# TIDA-00641_BlankSheet.net
KiCad netlist of a schematic drawn in Altium Designer
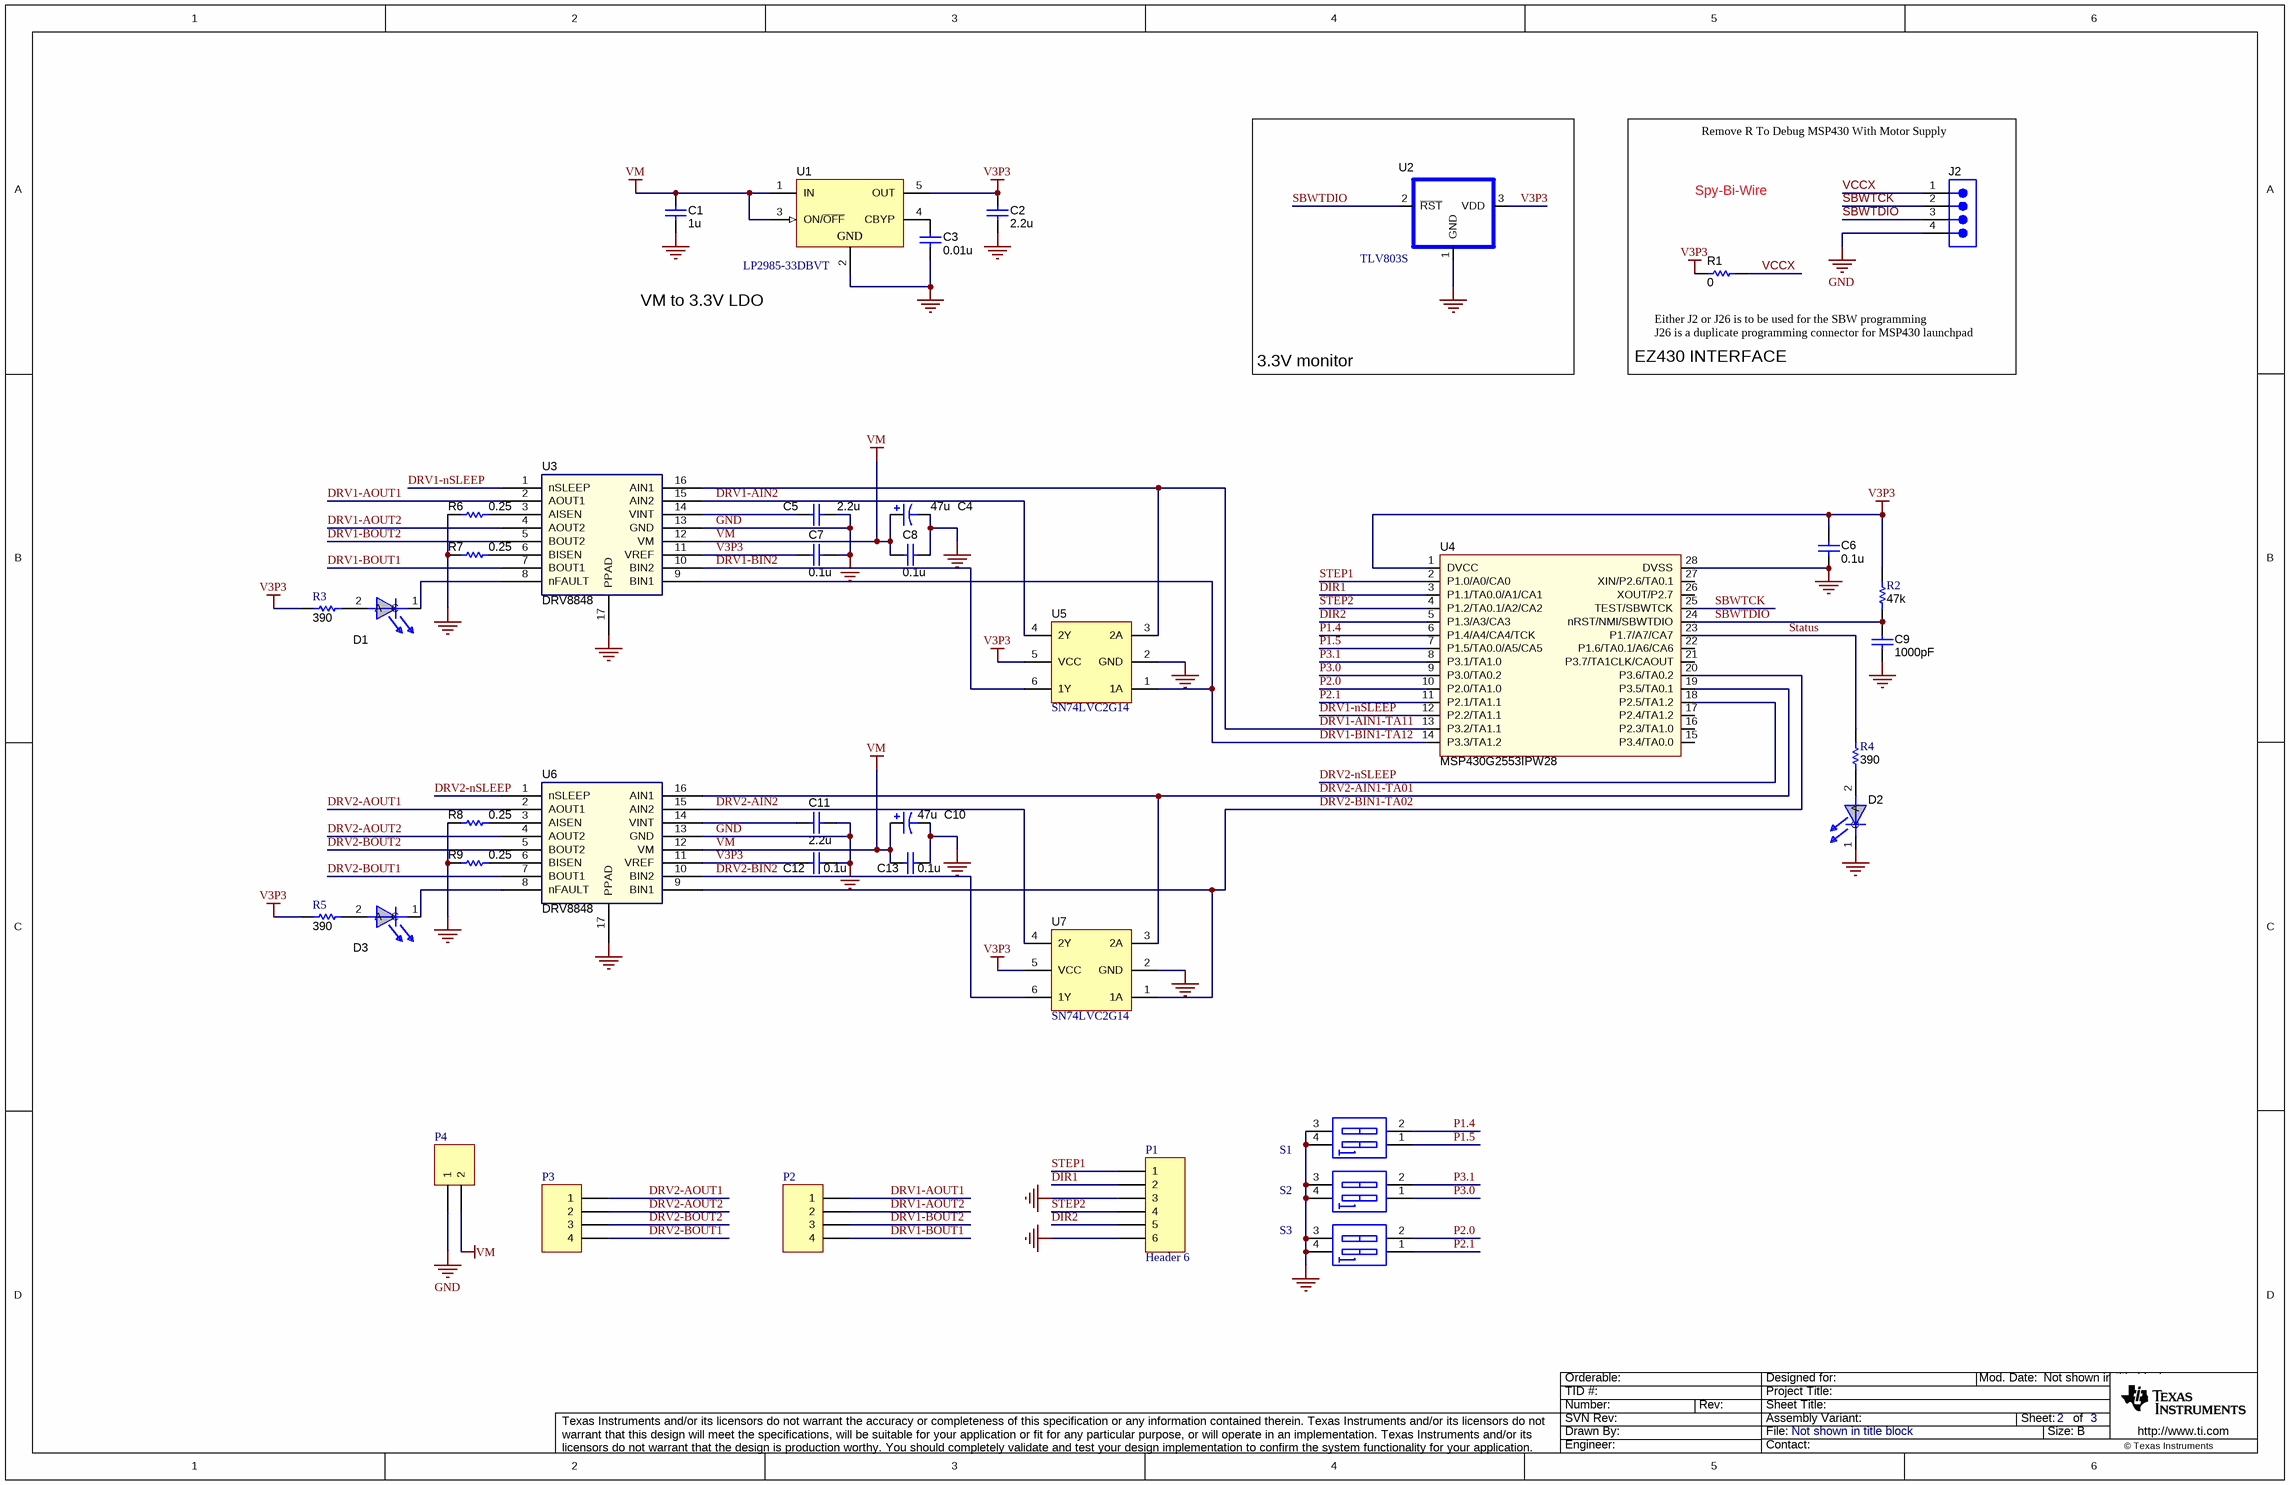
[diagram p0: TIDA-00641_BlankSheet.SchDoc]

(export (version "E")
  (design (tool "Eeschema 10.0.6"))
  (components
    (comp (ref "C1")
      (value "C0603C105K4PACTU")
      (footprint "0603L")
      (description "CAP, CERM, 1uF, 16V, +/-10%, X5R, 0603")
      (fields
        (field (name "MANUFACTURER") "Kemet")
        (field (name "VALUEDISPLAYED") "1u")
        (field (name "PUBLISHER") "Texas Instruments")
      )
      (libsource (lib "Capacitor_Ceramic") (part "C0603C105K4PACTU"))
    )
    (comp (ref "C2")
      (value "C0603C225K8PACTU")
      (footprint "0603L")
      (description "CAP, CERM, 2.2uF, 10V, +/-10%, X5R, 0603")
      (fields
        (field (name "VALUEDISPLAYED") "2.2u")
        (field (name "MANUFACTURER") "Kemet")
        (field (name "PUBLISHER") "Texas Instruments")
      )
      (libsource (lib "Capacitor_Ceramic") (part "C0603C225K8PACTU"))
    )
    (comp (ref "C3")
      (value "C0603C103J5RACTU")
      (footprint "0603L")
      (description "CAP, CERM, 0.01uF, 50V, +/-5%, X7R, 0603")
      (fields
        (field (name "MANUFACTURER") "Kemet")
        (field (name "VALUEDISPLAYED") "0.01u")
        (field (name "PUBLISHER") "Texas Instruments")
      )
      (libsource (lib "Capacitor_Ceramic") (part "C0603C103J5RACTU"))
    )
    (comp (ref "C4")
      (value "EEE-FK1E470P")
      (footprint "SM_RADIAL_D")
      (description "CAP, AL, 47uF, 25V, +/-20%, 0.36 ohm, SMD")
      (fields
        (field (name "VALUEDISPLAYED") "47u")
        (field (name "MANUFACTURER") "Panasonic")
        (field (name "PUBLISHER") "Texas Instruments")
      )
      (libsource (lib "Capacitor_Aluminum") (part "EEE-FK1E470P"))
    )
    (comp (ref "C5")
      (value "C0603C225M8PACTU")
      (footprint "0603L")
      (description "CAP, CERM, 2.2uF, 10V, +/-20%, X5R, 0603")
      (fields
        (field (name "VALUEDISPLAYED") "2.2u")
        (field (name "MANUFACTURER") "Kemet")
        (field (name "PUBLISHER") "Texas Instruments")
      )
      (libsource (lib "Capacitor_Ceramic") (part "C0603C225M8PACTU"))
    )
    (comp (ref "C6")
      (value "C0603C104K4RACTU")
      (footprint "0603L")
      (description "CAP, CERM, 0.1uF, 16V, +/-10%, X7R, 0603")
      (fields
        (field (name "VALUEDISPLAYED") "0.1u")
        (field (name "MANUFACTURER") "Kemet")
        (field (name "PUBLISHER") "Texas Instruments")
      )
      (libsource (lib "Capacitor_Ceramic") (part "C0603C104K4RACTU"))
    )
    (comp (ref "C7")
      (value "06033C104KAT2A")
      (footprint "0603L")
      (description "CAP, CERM, 0.1uF, 25V, +/-10%, X7R, 0603")
      (fields
        (field (name "VALUEDISPLAYED") "0.1u")
        (field (name "MANUFACTURER") "AVX")
        (field (name "PUBLISHER") "Texas Instruments")
      )
      (libsource (lib "Capacitor_Ceramic") (part "06033C104KAT2A"))
    )
    (comp (ref "C8")
      (value "06033C104KAT2A")
      (footprint "0603L")
      (description "CAP, CERM, 0.1uF, 25V, +/-10%, X7R, 0603")
      (fields
        (field (name "VALUEDISPLAYED") "0.1u")
        (field (name "MANUFACTURER") "AVX")
        (field (name "PUBLISHER") "Texas Instruments")
      )
      (libsource (lib "Capacitor_Ceramic") (part "06033C104KAT2A"))
    )
    (comp (ref "C9")
      (value "C0603C102K5RACTU")
      (footprint "0603L")
      (description "CAP, CERM, 1000pF, 50V, +/-10%, X7R, 0603")
      (fields
        (field (name "VALUEDISPLAYED") "1000pF")
        (field (name "MANUFACTURER") "Kemet")
        (field (name "PUBLISHER") "Texas Instruments")
      )
      (libsource (lib "Capacitor_Ceramic") (part "C0603C102K5RACTU"))
    )
    (comp (ref "C10")
      (value "EEE-FK1E470P")
      (footprint "SM_RADIAL_D")
      (description "CAP, AL, 47uF, 25V, +/-20%, 0.36 ohm, SMD")
      (fields
        (field (name "VALUEDISPLAYED") "47u")
        (field (name "MANUFACTURER") "Panasonic")
        (field (name "PUBLISHER") "Texas Instruments")
      )
      (libsource (lib "Capacitor_Aluminum") (part "EEE-FK1E470P"))
    )
    (comp (ref "C11")
      (value "C0603C225K8PACTU")
      (footprint "0603L")
      (description "CAP, CERM, 2.2uF, 10V, +/-10%, X5R, 0603")
      (fields
        (field (name "VALUEDISPLAYED") "2.2u")
        (field (name "MANUFACTURER") "Kemet")
        (field (name "PUBLISHER") "Texas Instruments")
      )
      (libsource (lib "Capacitor_Ceramic") (part "C0603C225K8PACTU"))
    )
    (comp (ref "C12")
      (value "06033C104KAT2A")
      (footprint "0603L")
      (description "CAP, CERM, 0.1uF, 25V, +/-10%, X7R, 0603")
      (fields
        (field (name "VALUEDISPLAYED") "0.1u")
        (field (name "MANUFACTURER") "AVX")
        (field (name "PUBLISHER") "Texas Instruments")
      )
      (libsource (lib "Capacitor_Ceramic") (part "06033C104KAT2A"))
    )
    (comp (ref "C13")
      (value "06033C104KAT2A")
      (footprint "0603L")
      (description "CAP, CERM, 0.1uF, 25V, +/-10%, X7R, 0603")
      (fields
        (field (name "VALUEDISPLAYED") "0.1u")
        (field (name "MANUFACTURER") "AVX")
        (field (name "PUBLISHER") "Texas Instruments")
      )
      (libsource (lib "Capacitor_Ceramic") (part "06033C104KAT2A"))
    )
    (comp (ref "D1")
      (value "LTST-C190KRKT")
      (footprint "LED603RED")
      (description "LED SUPER RED CLEAR 0603 SMD")
      (fields (field (name "MANUFACTURER") "Lite On"))
      (libsource (lib "PADSlegacy_Active") (part "D_LED_603_GRN"))
    )
    (comp (ref "D2")
      (value "LTST-C190GKT")
      (footprint "LED603GRN")
      (description "Diode, LED, Green, 2.1-V, 20-mA, 6-mcd")
      (fields (field (name "MANUFACTURER") "Lite On"))
      (libsource (lib "PADSlegacy_Active") (part "D_LED_603_GRN"))
    )
    (comp (ref "D3")
      (value "LTST-C190KRKT")
      (footprint "LED603RED")
      (description "LED SUPER RED CLEAR 0603 SMD")
      (fields (field (name "MANUFACTURER") "Lite On"))
      (libsource (lib "PADSlegacy_Active") (part "D_LED_603_GRN"))
    )
    (comp (ref "J2")
      (value "TSW-104-07-G-S")
      (footprint "HDR1X4")
      (description "Header, TH, 100mil, 4x1, Gold plated, 230 mil above insulator")
      (fields
        (field (name "MANUFACTURER") "Samtec, Inc.")
        (field (name "PUBLISHER") "Texas Instruments")
        (field (name "SYMBOLCREATOR") "a0412235")
      )
      (libsource (lib "Connectors") (part "TSW-104-07-G-S"))
    )
    (comp (ref "P1")
      (value "Header 6")
      (footprint "HDR1X6")
      (description "Header, 6-Pin")
      (fields (field (name "PUBLISHER") "Altium Limited"))
      (libsource (lib "Miscellaneous Connectors") (part "Header 6"))
    )
    (comp (ref "P2")
      (value "Header 4")
      (footprint "J4-3.81")
      (description "Header, 4-Pin")
      (fields (field (name "PUBLISHER") "Altium Limited"))
      (libsource (lib "Miscellaneous Connectors") (part "Header 4"))
    )
    (comp (ref "P3")
      (value "Header 4")
      (footprint "J4-3.81")
      (description "Header, 4-Pin")
      (fields (field (name "PUBLISHER") "Altium Limited"))
      (libsource (lib "Miscellaneous Connectors") (part "Header 4"))
    )
    (comp (ref "P4")
      (value "Header 2")
      (footprint "j2-3.81")
      (description "Header, 2-Pin")
      (fields (field (name "PUBLISHER") "Altium Limited"))
      (libsource (lib "Miscellaneous Connectors") (part "Header 2"))
    )
    (comp (ref "R1")
      (value "0")
      (footprint "0603L")
      (description "RES, 0 ohm, 5%, 0.1W, 0603")
      (fields
        (field (name "PARTNUMBER") "ERJ-3GEY0R00V")
        (field (name "MANUFACTURER") "Panasonic")
        (field (name "PUBLISHER") "Texas Instruments")
      )
      (libsource (lib "Resistor_0603") (part "ERJ-3GEY0R00V"))
    )
    (comp (ref "R2")
      (value "47k")
      (footprint "0603L")
      (description "RES, 47k ohm, 5%, 0.1W, 0603")
      (fields
        (field (name "PARTNUMBER") "CRCW060347K0JNEA")
        (field (name "MANUFACTURER") "Vishay-Dale")
        (field (name "PUBLISHER") "Texas Instruments")
      )
      (libsource (lib "Resistor_0603") (part "CRCW060347K0JNEA"))
    )
    (comp (ref "R3")
      (value "390")
      (footprint "0603L")
      (description "RES, 390 ohm, 1%, 0.1W, 0603")
      (fields
        (field (name "PARTNUMBER") "RC0603FR-07390RL")
        (field (name "MANUFACTURER") "Yageo America")
        (field (name "PUBLISHER") "Texas Instruments")
      )
      (libsource (lib "Resistor_0603") (part "RC0603FR-07390RL"))
    )
    (comp (ref "R4")
      (value "390")
      (footprint "0603L")
      (description "RES, 390 ohm, 1%, 0.1W, 0603")
      (fields
        (field (name "PARTNUMBER") "RC0603FR-07390RL")
        (field (name "MANUFACTURER") "Yageo America")
        (field (name "PUBLISHER") "Texas Instruments")
      )
      (libsource (lib "Resistor_0603") (part "RC0603FR-07390RL"))
    )
    (comp (ref "R5")
      (value "390")
      (footprint "0603L")
      (description "RES, 390 ohm, 1%, 0.1W, 0603")
      (fields
        (field (name "PARTNUMBER") "RC0603FR-07390RL")
        (field (name "MANUFACTURER") "Yageo America")
        (field (name "PUBLISHER") "Texas Instruments")
      )
      (libsource (lib "Resistor_0603") (part "RC0603FR-07390RL"))
    )
    (comp (ref "R6")
      (value "0.25")
      (footprint "2512M")
      (description "RES, 0.25 ohm, 1%, 2W, 2512")
      (fields
        (field (name "PARTNUMBER") "CSRN2512FKR250")
        (field (name "MANUFACTURER") "Stackpole Electronics Inc")
        (field (name "PUBLISHER") "Texas Instruments")
      )
      (libsource (lib "Resistor_OtherSMT") (part "CSRN2512FKR250"))
    )
    (comp (ref "R7")
      (value "0.25")
      (footprint "2512M")
      (description "RES, 0.25 ohm, 1%, 2W, 2512")
      (fields
        (field (name "PARTNUMBER") "CSRN2512FKR250")
        (field (name "MANUFACTURER") "Stackpole Electronics Inc")
        (field (name "PUBLISHER") "Texas Instruments")
      )
      (libsource (lib "Resistor_OtherSMT") (part "CSRN2512FKR250"))
    )
    (comp (ref "R8")
      (value "0.25")
      (footprint "2512M")
      (description "RES, 0.25 ohm, 1%, 2W, 2512")
      (fields
        (field (name "PARTNUMBER") "CSRN2512FKR250")
        (field (name "MANUFACTURER") "Stackpole Electronics Inc")
        (field (name "PUBLISHER") "Texas Instruments")
      )
      (libsource (lib "Resistor_OtherSMT") (part "CSRN2512FKR250"))
    )
    (comp (ref "R9")
      (value "0.25")
      (footprint "2512M")
      (description "RES, 0.25 ohm, 1%, 2W, 2512")
      (fields
        (field (name "PARTNUMBER") "CSRN2512FKR250")
        (field (name "MANUFACTURER") "Stackpole Electronics Inc")
        (field (name "PUBLISHER") "Texas Instruments")
      )
      (libsource (lib "Resistor_OtherSMT") (part "CSRN2512FKR250"))
    )
    (comp (ref "S1")
      (value "SW DIP-2")
      (footprint "DIP-4")
      (description "SWITCH TIN CONT 2 SEC 50V")
      (fields (field (name "PUBLISHER") "Altium Limited"))
      (libsource (lib "Miscellaneous Devices") (part "SW DIP-2"))
    )
    (comp (ref "S2")
      (value "SW DIP-2")
      (footprint "DIP-4")
      (description "SWITCH TIN CONT 2 SEC 50V")
      (fields (field (name "PUBLISHER") "Altium Limited"))
      (libsource (lib "Miscellaneous Devices") (part "SW DIP-2"))
    )
    (comp (ref "S3")
      (value "SW DIP-2")
      (footprint "DIP-4")
      (description "SWITCH TIN CONT 2 SEC 50V")
      (fields (field (name "PUBLISHER") "Altium Limited"))
      (libsource (lib "Miscellaneous Devices") (part "SW DIP-2"))
    )
    (comp (ref "U1")
      (value "LP2985-33DBVT")
      (footprint "MF05A_L")
      (description "Micropower 150 mA Low-Noise Ultra Low-Dropout Regulator, 5-pin SOT-23")
      (fields
        (field (name "PARTNUMBER") "LP2985IM5-3.3")
        (field (name "MANUFACTURER") "National Semiconductor")
        (field (name "PUBLISHER") "Altium Limited")
      )
      (libsource (lib "NSC LDO") (part "LP2985IM5-3.3"))
    )
    (comp (ref "U2")
      (value "TLV803S")
      (footprint "SOT-23")
      (description "IC VOLT SUPERVISR 2.93V SOT23-3")
      (fields (field (name "MANUFACTURER") "TI") (field (name "PARTNUMBER") "TLV803SDBZR"))
      (libsource (lib "PADSlegacy_PMP") (part "TLV803DBZ"))
    )
    (comp (ref "U3")
      (value "DRV8848")
      (footprint "PW0016S")
      (description "IC MOTOR DRIVER PAR 16HTSSOP")
      (fields
        (field (name "MANUFACTURER") "Used in BOM report")
        (field (name "MANUFACTURER_1") "Texas Instruments")
        (field (name "SYMBOLCREATOR") "Use a-id")
      )
      (libsource (lib "MDBU_Library_Elements") (part "DRV8848PWP"))
    )
    (comp (ref "U4")
      (value "MSP430G2553IPW28")
      (footprint "PW0028A_N")
      (description "IC MCU 16BIT 16KB FLASH 28TSSOP")
      (fields (field (name "MANUFACTURER") "TI"))
      (libsource (lib "DRV8865_EVM_E1") (part "MSP430G2553IPW28"))
    )
    (comp (ref "U5")
      (value "SN74LVC2G14")
      (footprint "DBV0006A_N")
      (description "Dual Schmitt-Trigger Inverter")
      (fields (field (name "MANUFACTURER") "Texas Instruments") (field (name "PARTNUMBER") "SN74LVC2G14DBVR"))
      (libsource (lib "TIDA-DRV8848PWM") (part "SN74LVC2G14"))
    )
    (comp (ref "U6")
      (value "DRV8848")
      (footprint "PW0016S")
      (description "IC MOTOR DRIVER PAR 16HTSSOP")
      (fields
        (field (name "MANUFACTURER") "Used in BOM report")
        (field (name "MANUFACTURER_1") "Texas Instruments")
        (field (name "SYMBOLCREATOR") "Use a-id")
      )
      (libsource (lib "MDBU_Library_Elements") (part "DRV8848PWP"))
    )
    (comp (ref "U7")
      (value "SN74LVC2G14")
      (footprint "DBV0006A_N")
      (description "Dual Schmitt-Trigger Inverter")
      (fields (field (name "MANUFACTURER") "Texas Instruments") (field (name "PARTNUMBER") "SN74LVC2G14DBVR"))
      (libsource (lib "TIDA-DRV8848PWM") (part "SN74LVC2G14"))
    )
  )
  (nets
    (net (code "1") (name "/DIR1") (class "Default")
      (node (ref "P1") (pin "2") (pinfunction "2_2") (pintype "passive"))
      (node (ref "U4") (pin "3") (pinfunction "P1.1/TA0.0/A1/CA1_3") (pintype "passive"))
    )
    (net (code "2") (name "/DIR2") (class "Default")
      (node (ref "P1") (pin "5") (pinfunction "5_5") (pintype "passive"))
      (node (ref "U4") (pin "5") (pinfunction "P1.3/A3/CA3_5") (pintype "passive"))
    )
    (net (code "3") (name "/DRV1-AIN1-TA11") (class "Default")
      (node (ref "U3") (pin "16") (pinfunction "AIN1_16") (pintype "passive"))
      (node (ref "U4") (pin "13") (pinfunction "P3.2/TA1.1_13") (pintype "passive"))
      (node (ref "U5") (pin "3") (pinfunction "2A_3") (pintype "passive"))
    )
    (net (code "4") (name "/DRV1-AIN2") (class "Default")
      (node (ref "U3") (pin "15") (pinfunction "AIN2_15") (pintype "passive"))
      (node (ref "U5") (pin "4") (pinfunction "2Y_4") (pintype "passive"))
    )
    (net (code "5") (name "/DRV1-AOUT1") (class "Default")
      (node (ref "P2") (pin "1") (pinfunction "1_1") (pintype "passive"))
      (node (ref "U3") (pin "2") (pinfunction "AOUT1_2") (pintype "passive"))
    )
    (net (code "6") (name "/DRV1-AOUT2") (class "Default")
      (node (ref "P2") (pin "2") (pinfunction "2_2") (pintype "passive"))
      (node (ref "U3") (pin "4") (pinfunction "AOUT2_4") (pintype "passive"))
    )
    (net (code "7") (name "/DRV1-BIN1-TA12") (class "Default")
      (node (ref "U3") (pin "9") (pinfunction "BIN1_9") (pintype "passive"))
      (node (ref "U4") (pin "14") (pinfunction "P3.3/TA1.2_14") (pintype "passive"))
      (node (ref "U5") (pin "1") (pinfunction "1A_1") (pintype "passive"))
    )
    (net (code "8") (name "/DRV1-BIN2") (class "Default")
      (node (ref "U3") (pin "10") (pinfunction "BIN2_10") (pintype "passive"))
      (node (ref "U5") (pin "6") (pinfunction "1Y_6") (pintype "passive"))
    )
    (net (code "9") (name "/DRV1-BOUT1") (class "Default")
      (node (ref "P2") (pin "4") (pinfunction "4_4") (pintype "passive"))
      (node (ref "U3") (pin "7") (pinfunction "BOUT1_7") (pintype "passive"))
    )
    (net (code "10") (name "/DRV1-BOUT2") (class "Default")
      (node (ref "P2") (pin "3") (pinfunction "3_3") (pintype "passive"))
      (node (ref "U3") (pin "5") (pinfunction "BOUT2_5") (pintype "passive"))
    )
    (net (code "11") (name "/DRV1-nSLEEP") (class "Default")
      (node (ref "U3") (pin "1") (pinfunction "nSLEEP_1") (pintype "passive"))
      (node (ref "U4") (pin "12") (pinfunction "P2.2/TA1.1_12") (pintype "passive"))
    )
    (net (code "12") (name "/DRV2-AIN1-TA01") (class "Default")
      (node (ref "U4") (pin "19") (pinfunction "P3.5/TA0.1_19") (pintype "passive"))
      (node (ref "U6") (pin "16") (pinfunction "AIN1_16") (pintype "passive"))
      (node (ref "U7") (pin "3") (pinfunction "2A_3") (pintype "passive"))
    )
    (net (code "13") (name "/DRV2-AIN2") (class "Default")
      (node (ref "U6") (pin "15") (pinfunction "AIN2_15") (pintype "passive"))
      (node (ref "U7") (pin "4") (pinfunction "2Y_4") (pintype "passive"))
    )
    (net (code "14") (name "/DRV2-AOUT1") (class "Default")
      (node (ref "P3") (pin "1") (pinfunction "1_1") (pintype "passive"))
      (node (ref "U6") (pin "2") (pinfunction "AOUT1_2") (pintype "passive"))
    )
    (net (code "15") (name "/DRV2-AOUT2") (class "Default")
      (node (ref "P3") (pin "2") (pinfunction "2_2") (pintype "passive"))
      (node (ref "U6") (pin "4") (pinfunction "AOUT2_4") (pintype "passive"))
    )
    (net (code "16") (name "/DRV2-BIN1-TA02") (class "Default")
      (node (ref "U4") (pin "20") (pinfunction "P3.6/TA0.2_20") (pintype "passive"))
      (node (ref "U6") (pin "9") (pinfunction "BIN1_9") (pintype "passive"))
      (node (ref "U7") (pin "1") (pinfunction "1A_1") (pintype "passive"))
    )
    (net (code "17") (name "/DRV2-BIN2") (class "Default")
      (node (ref "U6") (pin "10") (pinfunction "BIN2_10") (pintype "passive"))
      (node (ref "U7") (pin "6") (pinfunction "1Y_6") (pintype "passive"))
    )
    (net (code "18") (name "/DRV2-BOUT1") (class "Default")
      (node (ref "P3") (pin "4") (pinfunction "4_4") (pintype "passive"))
      (node (ref "U6") (pin "7") (pinfunction "BOUT1_7") (pintype "passive"))
    )
    (net (code "19") (name "/DRV2-BOUT2") (class "Default")
      (node (ref "P3") (pin "3") (pinfunction "3_3") (pintype "passive"))
      (node (ref "U6") (pin "5") (pinfunction "BOUT2_5") (pintype "passive"))
    )
    (net (code "20") (name "/DRV2-nSLEEP") (class "Default")
      (node (ref "U4") (pin "18") (pinfunction "P2.5/TA1.2_18") (pintype "passive"))
      (node (ref "U6") (pin "1") (pinfunction "nSLEEP_1") (pintype "passive"))
    )
    (net (code "21") (name "/P1.4") (class "Default")
      (node (ref "S1") (pin "2") (pinfunction "A2_2") (pintype "passive"))
      (node (ref "U4") (pin "6") (pinfunction "P1.4/A4/CA4/TCK_6") (pintype "passive"))
    )
    (net (code "22") (name "/P1.5") (class "Default")
      (node (ref "S1") (pin "1") (pinfunction "A1_1") (pintype "passive"))
      (node (ref "U4") (pin "7") (pinfunction "P1.5/TA0.0/A5/CA5_7") (pintype "passive"))
    )
    (net (code "23") (name "/P2.0") (class "Default")
      (node (ref "S3") (pin "2") (pinfunction "A2_2") (pintype "passive"))
      (node (ref "U4") (pin "10") (pinfunction "P2.0/TA1.0_10") (pintype "passive"))
    )
    (net (code "24") (name "/P2.1") (class "Default")
      (node (ref "S3") (pin "1") (pinfunction "A1_1") (pintype "passive"))
      (node (ref "U4") (pin "11") (pinfunction "P2.1/TA1.1_11") (pintype "passive"))
    )
    (net (code "25") (name "/P3.0") (class "Default")
      (node (ref "S2") (pin "1") (pinfunction "A1_1") (pintype "passive"))
      (node (ref "U4") (pin "9") (pinfunction "P3.0/TA0.2_9") (pintype "passive"))
    )
    (net (code "26") (name "/P3.1") (class "Default")
      (node (ref "S2") (pin "2") (pinfunction "A2_2") (pintype "passive"))
      (node (ref "U4") (pin "8") (pinfunction "P3.1/TA1.0_8") (pintype "passive"))
    )
    (net (code "27") (name "/SBWTCK") (class "Default")
      (node (ref "J2") (pin "2") (pinfunction "2_2") (pintype "passive"))
      (node (ref "U4") (pin "25") (pinfunction "TEST/SBWTCK_25") (pintype "passive"))
    )
    (net (code "28") (name "/SBWTDIO") (class "Default")
      (node (ref "C9") (pin "2") (pinfunction "2_2") (pintype "passive"))
      (node (ref "J2") (pin "3") (pinfunction "3_3") (pintype "passive"))
      (node (ref "R2") (pin "2") (pinfunction "2_2") (pintype "passive"))
      (node (ref "U2") (pin "2") (pinfunction "RST_2") (pintype "passive"))
      (node (ref "U4") (pin "24") (pinfunction "nRST/NMI/SBWTDIO_24") (pintype "passive"))
    )
    (net (code "29") (name "/STEP1") (class "Default")
      (node (ref "P1") (pin "1") (pinfunction "1_1") (pintype "passive"))
      (node (ref "U4") (pin "2") (pinfunction "P1.0/A0/CA0_2") (pintype "passive"))
    )
    (net (code "30") (name "/STEP2") (class "Default")
      (node (ref "P1") (pin "4") (pinfunction "4_4") (pintype "passive"))
      (node (ref "U4") (pin "4") (pinfunction "P1.2/TA0.1/A2/CA2_4") (pintype "passive"))
    )
    (net (code "31") (name "/Status") (class "Default")
      (node (ref "R4") (pin "2") (pinfunction "2_2") (pintype "passive"))
      (node (ref "U4") (pin "23") (pinfunction "P1.7/A7/CA7_23") (pintype "passive"))
    )
    (net (code "32") (name "/VCCX") (class "Default")
      (node (ref "J2") (pin "1") (pinfunction "1_1") (pintype "passive"))
      (node (ref "R1") (pin "2") (pinfunction "2_2") (pintype "passive"))
    )
    (net (code "33") (name "GND") (class "Default")
      (node (ref "C1") (pin "2") (pinfunction "2_2") (pintype "passive"))
      (node (ref "C10") (pin "2") (pinfunction "-_2") (pintype "passive"))
      (node (ref "C11") (pin "2") (pinfunction "2_2") (pintype "passive"))
      (node (ref "C12") (pin "1") (pinfunction "1_1") (pintype "passive"))
      (node (ref "C13") (pin "1") (pinfunction "1_1") (pintype "passive"))
      (node (ref "C2") (pin "1") (pinfunction "1_1") (pintype "passive"))
      (node (ref "C3") (pin "2") (pinfunction "2_2") (pintype "passive"))
      (node (ref "C4") (pin "2") (pinfunction "-_2") (pintype "passive"))
      (node (ref "C5") (pin "2") (pinfunction "2_2") (pintype "passive"))
      (node (ref "C6") (pin "1") (pinfunction "1_1") (pintype "passive"))
      (node (ref "C7") (pin "1") (pinfunction "1_1") (pintype "passive"))
      (node (ref "C8") (pin "1") (pinfunction "1_1") (pintype "passive"))
      (node (ref "C9") (pin "1") (pinfunction "1_1") (pintype "passive"))
      (node (ref "D2") (pin "1") (pinfunction "C_1") (pintype "passive"))
      (node (ref "J2") (pin "4") (pinfunction "4_4") (pintype "passive"))
      (node (ref "P1") (pin "3") (pinfunction "3_3") (pintype "passive"))
      (node (ref "P1") (pin "6") (pinfunction "6_6") (pintype "passive"))
      (node (ref "P4") (pin "1") (pinfunction "1_1") (pintype "passive"))
      (node (ref "R6") (pin "1") (pinfunction "1_1") (pintype "passive"))
      (node (ref "R7") (pin "1") (pinfunction "1_1") (pintype "passive"))
      (node (ref "R8") (pin "1") (pinfunction "1_1") (pintype "passive"))
      (node (ref "R9") (pin "1") (pinfunction "1_1") (pintype "passive"))
      (node (ref "S1") (pin "3") (pinfunction "B2_3") (pintype "passive"))
      (node (ref "S1") (pin "4") (pinfunction "B1_4") (pintype "passive"))
      (node (ref "S2") (pin "3") (pinfunction "B2_3") (pintype "passive"))
      (node (ref "S2") (pin "4") (pinfunction "B1_4") (pintype "passive"))
      (node (ref "S3") (pin "3") (pinfunction "B2_3") (pintype "passive"))
      (node (ref "S3") (pin "4") (pinfunction "B1_4") (pintype "passive"))
      (node (ref "U1") (pin "2") (pinfunction "GND_2") (pintype "power_in"))
      (node (ref "U2") (pin "1") (pinfunction "GND_1") (pintype "passive"))
      (node (ref "U3") (pin "13") (pinfunction "GND_13") (pintype "passive"))
      (node (ref "U3") (pin "17") (pinfunction "PPAD_17") (pintype "passive"))
      (node (ref "U4") (pin "28") (pinfunction "DVSS_28") (pintype "passive"))
      (node (ref "U5") (pin "2") (pinfunction "GND_2") (pintype "power_in"))
      (node (ref "U6") (pin "13") (pinfunction "GND_13") (pintype "passive"))
      (node (ref "U6") (pin "17") (pinfunction "PPAD_17") (pintype "passive"))
      (node (ref "U7") (pin "2") (pinfunction "GND_2") (pintype "power_in"))
    )
    (net (code "34") (name "Net-(D1-A)") (class "Default")
      (node (ref "D1") (pin "2") (pinfunction "A_2") (pintype "passive"))
      (node (ref "R3") (pin "1") (pinfunction "1_1") (pintype "passive"))
    )
    (net (code "35") (name "Net-(D1-C)") (class "Default")
      (node (ref "D1") (pin "1") (pinfunction "C_1") (pintype "passive"))
      (node (ref "U3") (pin "8") (pinfunction "nFAULT_8") (pintype "passive"))
    )
    (net (code "36") (name "Net-(D2-A)") (class "Default")
      (node (ref "D2") (pin "2") (pinfunction "A_2") (pintype "passive"))
      (node (ref "R4") (pin "1") (pinfunction "1_1") (pintype "passive"))
    )
    (net (code "37") (name "Net-(D3-A)") (class "Default")
      (node (ref "D3") (pin "2") (pinfunction "A_2") (pintype "passive"))
      (node (ref "R5") (pin "1") (pinfunction "1_1") (pintype "passive"))
    )
    (net (code "38") (name "Net-(D3-C)") (class "Default")
      (node (ref "D3") (pin "1") (pinfunction "C_1") (pintype "passive"))
      (node (ref "U6") (pin "8") (pinfunction "nFAULT_8") (pintype "passive"))
    )
    (net (code "39") (name "Net-(U1-CBYP)") (class "Default")
      (node (ref "C3") (pin "1") (pinfunction "1_1") (pintype "passive"))
      (node (ref "U1") (pin "4") (pinfunction "CBYP_4") (pintype "passive"))
    )
    (net (code "40") (name "Net-(U3-AISEN)") (class "Default")
      (node (ref "R6") (pin "2") (pinfunction "2_2") (pintype "passive"))
      (node (ref "U3") (pin "3") (pinfunction "AISEN_3") (pintype "passive"))
    )
    (net (code "41") (name "Net-(U3-BISEN)") (class "Default")
      (node (ref "R7") (pin "2") (pinfunction "2_2") (pintype "passive"))
      (node (ref "U3") (pin "6") (pinfunction "BISEN_6") (pintype "passive"))
    )
    (net (code "42") (name "Net-(U3-VINT)") (class "Default")
      (node (ref "C5") (pin "1") (pinfunction "1_1") (pintype "passive"))
      (node (ref "U3") (pin "14") (pinfunction "VINT_14") (pintype "passive"))
    )
    (net (code "43") (name "Net-(U6-AISEN)") (class "Default")
      (node (ref "R8") (pin "2") (pinfunction "2_2") (pintype "passive"))
      (node (ref "U6") (pin "3") (pinfunction "AISEN_3") (pintype "passive"))
    )
    (net (code "44") (name "Net-(U6-BISEN)") (class "Default")
      (node (ref "R9") (pin "2") (pinfunction "2_2") (pintype "passive"))
      (node (ref "U6") (pin "6") (pinfunction "BISEN_6") (pintype "passive"))
    )
    (net (code "45") (name "Net-(U6-VINT)") (class "Default")
      (node (ref "C11") (pin "1") (pinfunction "1_1") (pintype "passive"))
      (node (ref "U6") (pin "14") (pinfunction "VINT_14") (pintype "passive"))
    )
    (net (code "46") (name "V3P3") (class "Default")
      (node (ref "C12") (pin "2") (pinfunction "2_2") (pintype "passive"))
      (node (ref "C2") (pin "2") (pinfunction "2_2") (pintype "passive"))
      (node (ref "C6") (pin "2") (pinfunction "2_2") (pintype "passive"))
      (node (ref "C7") (pin "2") (pinfunction "2_2") (pintype "passive"))
      (node (ref "R1") (pin "1") (pinfunction "1_1") (pintype "passive"))
      (node (ref "R2") (pin "1") (pinfunction "1_1") (pintype "passive"))
      (node (ref "R3") (pin "2") (pinfunction "2_2") (pintype "passive"))
      (node (ref "R5") (pin "2") (pinfunction "2_2") (pintype "passive"))
      (node (ref "U1") (pin "5") (pinfunction "OUT_5") (pintype "power_in"))
      (node (ref "U2") (pin "3") (pinfunction "VDD_3") (pintype "passive"))
      (node (ref "U3") (pin "11") (pinfunction "VREF_11") (pintype "passive"))
      (node (ref "U4") (pin "1") (pinfunction "DVCC_1") (pintype "passive"))
      (node (ref "U5") (pin "5") (pinfunction "VCC_5") (pintype "power_in"))
      (node (ref "U6") (pin "11") (pinfunction "VREF_11") (pintype "passive"))
      (node (ref "U7") (pin "5") (pinfunction "VCC_5") (pintype "power_in"))
    )
    (net (code "47") (name "VM") (class "Default")
      (node (ref "C1") (pin "1") (pinfunction "1_1") (pintype "passive"))
      (node (ref "C10") (pin "1") (pinfunction "+_1") (pintype "passive"))
      (node (ref "C13") (pin "2") (pinfunction "2_2") (pintype "passive"))
      (node (ref "C4") (pin "1") (pinfunction "+_1") (pintype "passive"))
      (node (ref "C8") (pin "2") (pinfunction "2_2") (pintype "passive"))
      (node (ref "P4") (pin "2") (pinfunction "2_2") (pintype "passive"))
      (node (ref "U1") (pin "1") (pinfunction "IN_1") (pintype "power_in"))
      (node (ref "U1") (pin "3") (pinfunction "ON/~{OFF}_3") (pintype "input"))
      (node (ref "U3") (pin "12") (pinfunction "VM_12") (pintype "passive"))
      (node (ref "U6") (pin "12") (pinfunction "VM_12") (pintype "passive"))
    )
    (net (code "48") (name "unconnected-(U4-P1.6{slash}TA0.1{slash}A6{slash}CA6-Pad22)") (class "Default")
      (node (ref "U4") (pin "22") (pinfunction "P1.6/TA0.1/A6/CA6_22") (pintype "passive"))
    )
    (net (code "49") (name "unconnected-(U4-P2.3{slash}TA1.0-Pad16)") (class "Default")
      (node (ref "U4") (pin "16") (pinfunction "P2.3/TA1.0_16") (pintype "passive"))
    )
    (net (code "50") (name "unconnected-(U4-P2.4{slash}TA1.2-Pad17)") (class "Default")
      (node (ref "U4") (pin "17") (pinfunction "P2.4/TA1.2_17") (pintype "passive"))
    )
    (net (code "51") (name "unconnected-(U4-P3.4{slash}TA0.0-Pad15)") (class "Default")
      (node (ref "U4") (pin "15") (pinfunction "P3.4/TA0.0_15") (pintype "passive"))
    )
    (net (code "52") (name "unconnected-(U4-P3.7{slash}TA1CLK{slash}CAOUT-Pad21)") (class "Default")
      (node (ref "U4") (pin "21") (pinfunction "P3.7/TA1CLK/CAOUT_21") (pintype "passive"))
    )
    (net (code "53") (name "unconnected-(U4-XIN{slash}P2.6{slash}TA0.1-Pad27)") (class "Default")
      (node (ref "U4") (pin "27") (pinfunction "XIN/P2.6/TA0.1_27") (pintype "passive"))
    )
    (net (code "54") (name "unconnected-(U4-XOUT{slash}P2.7-Pad26)") (class "Default")
      (node (ref "U4") (pin "26") (pinfunction "XOUT/P2.7_26") (pintype "passive"))
    )
  )
)
